# ws2812_Sqaure_V01.net
KiCad netlist of a schematic drawn in EAGLE
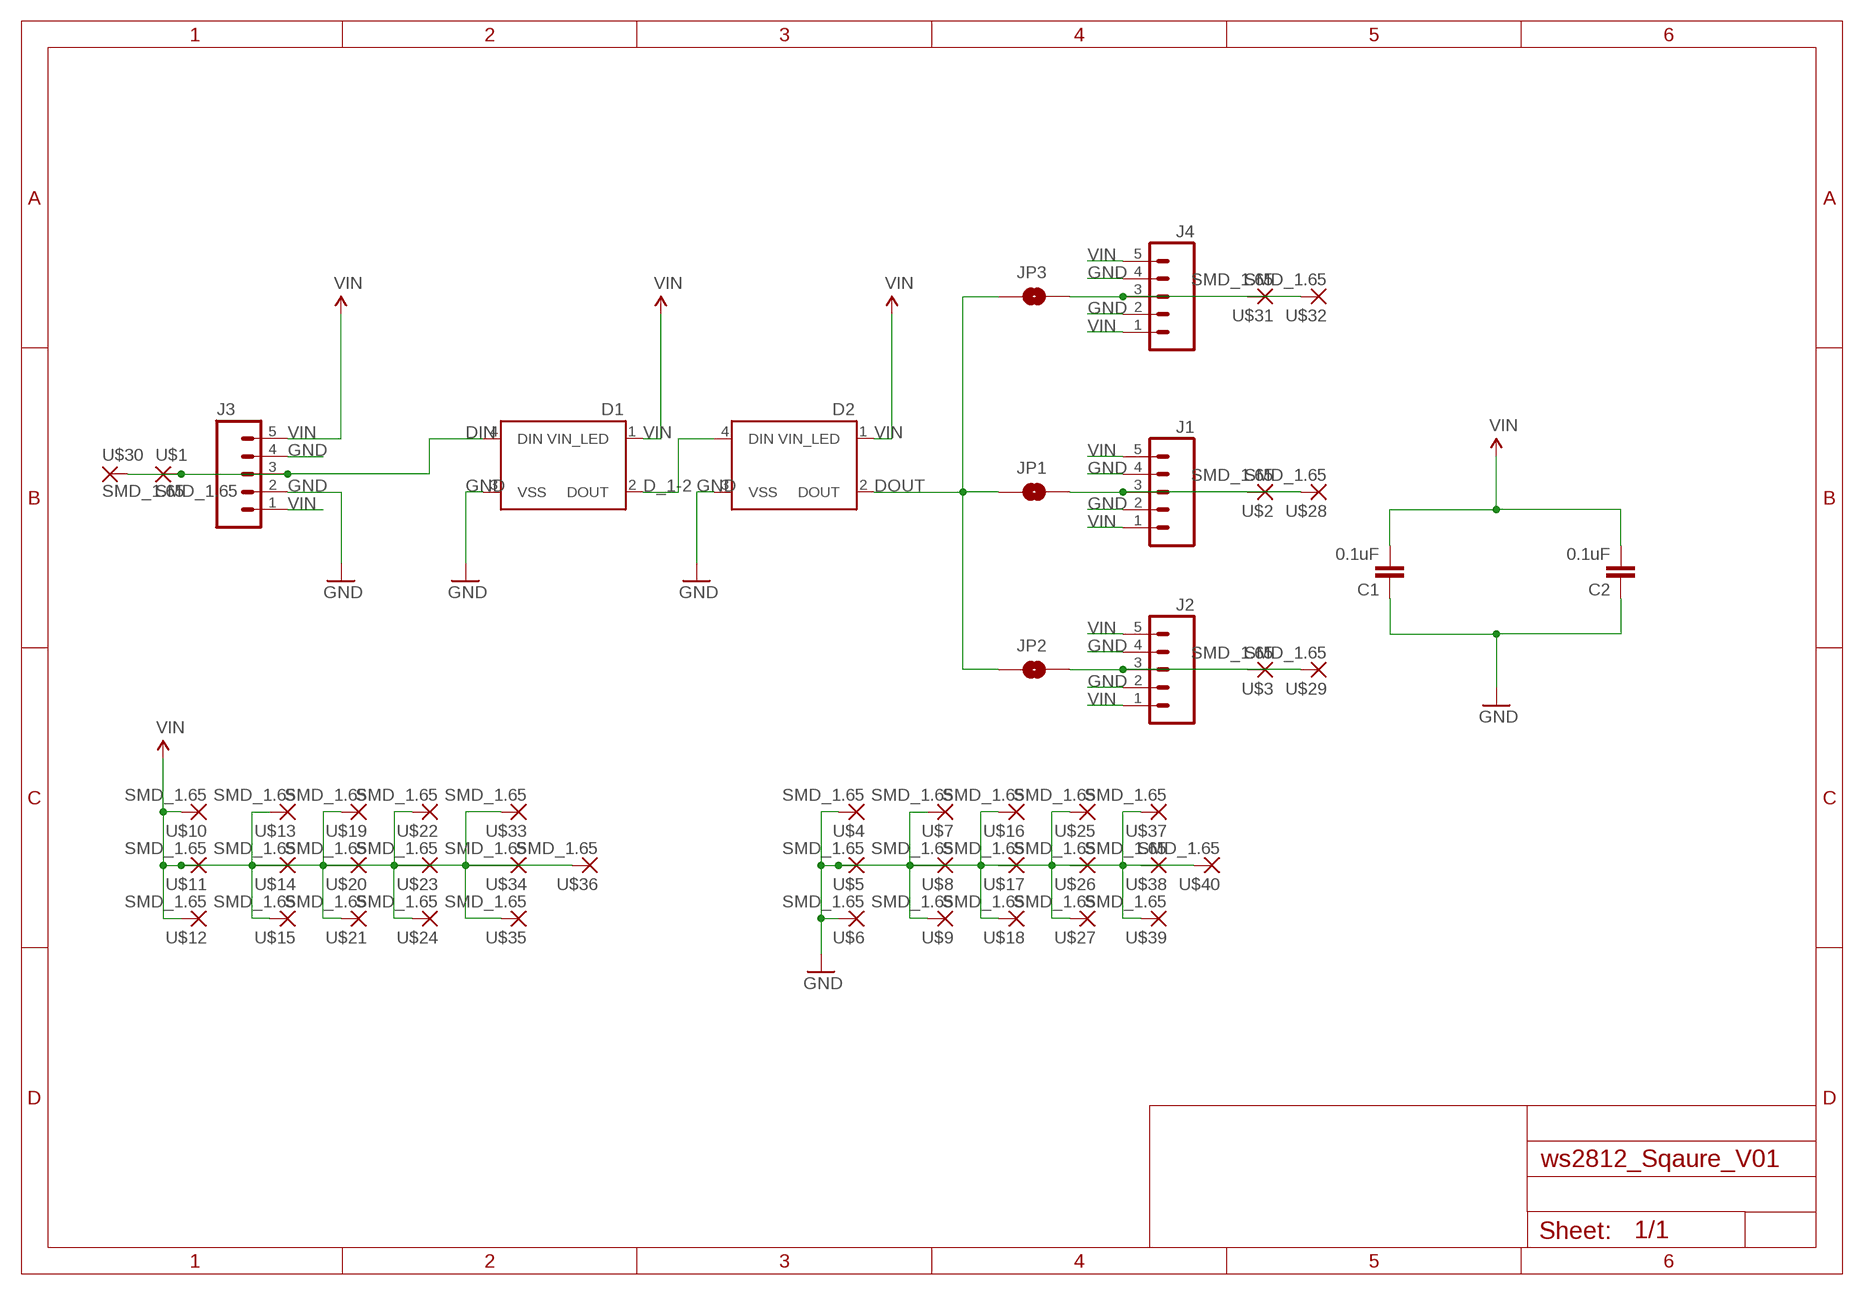
[diagram p0: schematic, sheet 1]

(export (version "E")
  (design (tool "Eeschema 10.0.6"))
  (components
    (comp (ref "C1")
      (value "0.1uF")
      (footprint "eagle-import:0805")
      (libsource (lib "eagle-import") (part "CAP0805"))
    )
    (comp (ref "C2")
      (value "0.1uF")
      (footprint "eagle-import:0805")
      (libsource (lib "eagle-import") (part "CAP0805"))
    )
    (comp (ref "D1")
      (value "WS2812B")
      (footprint "eagle-import:WS2812B")
      (libsource (lib "eagle-import") (part "WS2812B"))
    )
    (comp (ref "D2")
      (value "WS2812B")
      (footprint "eagle-import:WS2812B")
      (libsource (lib "eagle-import") (part "WS2812B"))
    )
    (comp (ref "J1")
      (value "M05NO_SILK")
      (footprint "eagle-import:1X05_NO_SILK")
      (libsource (lib "eagle-import") (part "M05NO_SILK"))
    )
    (comp (ref "J2")
      (value "M05NO_SILK")
      (footprint "eagle-import:1X05_NO_SILK")
      (libsource (lib "eagle-import") (part "M05NO_SILK"))
    )
    (comp (ref "J3")
      (value "M05NO_SILK")
      (footprint "eagle-import:1X05_NO_SILK")
      (libsource (lib "eagle-import") (part "M05NO_SILK"))
    )
    (comp (ref "J4")
      (value "M05NO_SILK")
      (footprint "eagle-import:1X05_NO_SILK")
      (libsource (lib "eagle-import") (part "M05NO_SILK"))
    )
    (comp (ref "JP1")
      (value "JUMPER-PAD-2-NOYES_SILK")
      (footprint "eagle-import:PAD-JUMPER-2-NO_YES_SILK")
      (libsource (lib "eagle-import") (part "JUMPER-PAD-2-NOYES_SILK"))
    )
    (comp (ref "JP2")
      (value "JUMPER-PAD-2-NOYES_SILK")
      (footprint "eagle-import:PAD-JUMPER-2-NO_YES_SILK")
      (libsource (lib "eagle-import") (part "JUMPER-PAD-2-NOYES_SILK"))
    )
    (comp (ref "JP3")
      (value "JUMPER-PAD-2-NOYES_SILK")
      (footprint "eagle-import:PAD-JUMPER-2-NO_YES_SILK")
      (libsource (lib "eagle-import") (part "JUMPER-PAD-2-NOYES_SILK"))
    )
    (comp (ref "U$1")
      (value "SMD_1.65")
      (footprint "eagle-import:SMD_PTH_1.65")
      (libsource (lib "eagle-import") (part "SMD_1.65"))
    )
    (comp (ref "U$2")
      (value "SMD_1.65")
      (footprint "eagle-import:SMD_PTH_1.65")
      (libsource (lib "eagle-import") (part "SMD_1.65"))
    )
    (comp (ref "U$3")
      (value "SMD_1.65")
      (footprint "eagle-import:SMD_PTH_1.65")
      (libsource (lib "eagle-import") (part "SMD_1.65"))
    )
    (comp (ref "U$4")
      (value "SMD_1.65")
      (footprint "eagle-import:SMD_PTH_1.65")
      (libsource (lib "eagle-import") (part "SMD_1.65"))
    )
    (comp (ref "U$5")
      (value "SMD_1.65")
      (footprint "eagle-import:SMD_PTH_1.65")
      (libsource (lib "eagle-import") (part "SMD_1.65"))
    )
    (comp (ref "U$6")
      (value "SMD_1.65")
      (footprint "eagle-import:SMD_PTH_1.65")
      (libsource (lib "eagle-import") (part "SMD_1.65"))
    )
    (comp (ref "U$7")
      (value "SMD_1.65")
      (footprint "eagle-import:SMD_PTH_1.65")
      (libsource (lib "eagle-import") (part "SMD_1.65"))
    )
    (comp (ref "U$8")
      (value "SMD_1.65")
      (footprint "eagle-import:SMD_PTH_1.65")
      (libsource (lib "eagle-import") (part "SMD_1.65"))
    )
    (comp (ref "U$9")
      (value "SMD_1.65")
      (footprint "eagle-import:SMD_PTH_1.65")
      (libsource (lib "eagle-import") (part "SMD_1.65"))
    )
    (comp (ref "U$10")
      (value "SMD_1.65")
      (footprint "eagle-import:SMD_PTH_1.65")
      (libsource (lib "eagle-import") (part "SMD_1.65"))
    )
    (comp (ref "U$11")
      (value "SMD_1.65")
      (footprint "eagle-import:SMD_PTH_1.65")
      (libsource (lib "eagle-import") (part "SMD_1.65"))
    )
    (comp (ref "U$12")
      (value "SMD_1.65")
      (footprint "eagle-import:SMD_PTH_1.65")
      (libsource (lib "eagle-import") (part "SMD_1.65"))
    )
    (comp (ref "U$13")
      (value "SMD_1.65")
      (footprint "eagle-import:SMD_PTH_1.65")
      (libsource (lib "eagle-import") (part "SMD_1.65"))
    )
    (comp (ref "U$14")
      (value "SMD_1.65")
      (footprint "eagle-import:SMD_PTH_1.65")
      (libsource (lib "eagle-import") (part "SMD_1.65"))
    )
    (comp (ref "U$15")
      (value "SMD_1.65")
      (footprint "eagle-import:SMD_PTH_1.65")
      (libsource (lib "eagle-import") (part "SMD_1.65"))
    )
    (comp (ref "U$16")
      (value "SMD_1.65")
      (footprint "eagle-import:SMD_PTH_1.65")
      (libsource (lib "eagle-import") (part "SMD_1.65"))
    )
    (comp (ref "U$17")
      (value "SMD_1.65")
      (footprint "eagle-import:SMD_PTH_1.65")
      (libsource (lib "eagle-import") (part "SMD_1.65"))
    )
    (comp (ref "U$18")
      (value "SMD_1.65")
      (footprint "eagle-import:SMD_PTH_1.65")
      (libsource (lib "eagle-import") (part "SMD_1.65"))
    )
    (comp (ref "U$19")
      (value "SMD_1.65")
      (footprint "eagle-import:SMD_PTH_1.65")
      (libsource (lib "eagle-import") (part "SMD_1.65"))
    )
    (comp (ref "U$20")
      (value "SMD_1.65")
      (footprint "eagle-import:SMD_PTH_1.65")
      (libsource (lib "eagle-import") (part "SMD_1.65"))
    )
    (comp (ref "U$21")
      (value "SMD_1.65")
      (footprint "eagle-import:SMD_PTH_1.65")
      (libsource (lib "eagle-import") (part "SMD_1.65"))
    )
    (comp (ref "U$22")
      (value "SMD_1.65")
      (footprint "eagle-import:SMD_PTH_1.65")
      (libsource (lib "eagle-import") (part "SMD_1.65"))
    )
    (comp (ref "U$23")
      (value "SMD_1.65")
      (footprint "eagle-import:SMD_PTH_1.65")
      (libsource (lib "eagle-import") (part "SMD_1.65"))
    )
    (comp (ref "U$24")
      (value "SMD_1.65")
      (footprint "eagle-import:SMD_PTH_1.65")
      (libsource (lib "eagle-import") (part "SMD_1.65"))
    )
    (comp (ref "U$25")
      (value "SMD_1.65")
      (footprint "eagle-import:SMD_PTH_1.65")
      (libsource (lib "eagle-import") (part "SMD_1.65"))
    )
    (comp (ref "U$26")
      (value "SMD_1.65")
      (footprint "eagle-import:SMD_PTH_1.65")
      (libsource (lib "eagle-import") (part "SMD_1.65"))
    )
    (comp (ref "U$27")
      (value "SMD_1.65")
      (footprint "eagle-import:SMD_PTH_1.65")
      (libsource (lib "eagle-import") (part "SMD_1.65"))
    )
    (comp (ref "U$28")
      (value "SMD_1.65")
      (footprint "eagle-import:SMD_PTH_1.65")
      (libsource (lib "eagle-import") (part "SMD_1.65"))
    )
    (comp (ref "U$29")
      (value "SMD_1.65")
      (footprint "eagle-import:SMD_PTH_1.65")
      (libsource (lib "eagle-import") (part "SMD_1.65"))
    )
    (comp (ref "U$30")
      (value "SMD_1.65")
      (footprint "eagle-import:SMD_PTH_1.65")
      (libsource (lib "eagle-import") (part "SMD_1.65"))
    )
    (comp (ref "U$31")
      (value "SMD_1.65")
      (footprint "eagle-import:SMD_PTH_1.65")
      (libsource (lib "eagle-import") (part "SMD_1.65"))
    )
    (comp (ref "U$32")
      (value "SMD_1.65")
      (footprint "eagle-import:SMD_PTH_1.65")
      (libsource (lib "eagle-import") (part "SMD_1.65"))
    )
    (comp (ref "U$33")
      (value "SMD_1.65")
      (footprint "eagle-import:SMD_PTH_1.65")
      (libsource (lib "eagle-import") (part "SMD_1.65"))
    )
    (comp (ref "U$34")
      (value "SMD_1.65")
      (footprint "eagle-import:SMD_PTH_1.65")
      (libsource (lib "eagle-import") (part "SMD_1.65"))
    )
    (comp (ref "U$35")
      (value "SMD_1.65")
      (footprint "eagle-import:SMD_PTH_1.65")
      (libsource (lib "eagle-import") (part "SMD_1.65"))
    )
    (comp (ref "U$36")
      (value "SMD_1.65")
      (footprint "eagle-import:SMD_PTH_1.65")
      (libsource (lib "eagle-import") (part "SMD_1.65"))
    )
    (comp (ref "U$37")
      (value "SMD_1.65")
      (footprint "eagle-import:SMD_PTH_1.65")
      (libsource (lib "eagle-import") (part "SMD_1.65"))
    )
    (comp (ref "U$38")
      (value "SMD_1.65")
      (footprint "eagle-import:SMD_PTH_1.65")
      (libsource (lib "eagle-import") (part "SMD_1.65"))
    )
    (comp (ref "U$39")
      (value "SMD_1.65")
      (footprint "eagle-import:SMD_PTH_1.65")
      (libsource (lib "eagle-import") (part "SMD_1.65"))
    )
    (comp (ref "U$40")
      (value "SMD_1.65")
      (footprint "eagle-import:SMD_PTH_1.65")
      (libsource (lib "eagle-import") (part "SMD_1.65"))
    )
  )
  (nets
    (net (code "1") (name "/DIN") (class "Default")
      (node (ref "D1") (pin "4") (pinfunction "DIN_4") (pintype "input"))
      (node (ref "J3") (pin "3") (pinfunction "3_3") (pintype "passive"))
      (node (ref "U$1") (pin "P$1") (pinfunction "P_P$1") (pintype "passive"))
      (node (ref "U$30") (pin "P$1") (pinfunction "P_P$1") (pintype "passive"))
    )
    (net (code "2") (name "/DOUT") (class "Default")
      (node (ref "D2") (pin "2") (pinfunction "DOUT_2") (pintype "output"))
      (node (ref "JP1") (pin "1") (pinfunction "1_1") (pintype "passive"))
      (node (ref "JP2") (pin "1") (pinfunction "1_1") (pintype "passive"))
      (node (ref "JP3") (pin "1") (pinfunction "1_1") (pintype "passive"))
    )
    (net (code "3") (name "/D_1-2") (class "Default")
      (node (ref "D1") (pin "2") (pinfunction "DOUT_2") (pintype "output"))
      (node (ref "D2") (pin "4") (pinfunction "DIN_4") (pintype "input"))
    )
    (net (code "4") (name "GND") (class "Default")
      (node (ref "C1") (pin "1") (pinfunction "1_1") (pintype "passive"))
      (node (ref "C2") (pin "1") (pinfunction "1_1") (pintype "passive"))
      (node (ref "D1") (pin "3") (pinfunction "VSS_3") (pintype "power_in"))
      (node (ref "D2") (pin "3") (pinfunction "VSS_3") (pintype "power_in"))
      (node (ref "J1") (pin "2") (pinfunction "2_2") (pintype "passive"))
      (node (ref "J1") (pin "4") (pinfunction "4_4") (pintype "passive"))
      (node (ref "J2") (pin "2") (pinfunction "2_2") (pintype "passive"))
      (node (ref "J2") (pin "4") (pinfunction "4_4") (pintype "passive"))
      (node (ref "J3") (pin "2") (pinfunction "2_2") (pintype "passive"))
      (node (ref "J3") (pin "4") (pinfunction "4_4") (pintype "passive"))
      (node (ref "J4") (pin "2") (pinfunction "2_2") (pintype "passive"))
      (node (ref "J4") (pin "4") (pinfunction "4_4") (pintype "passive"))
      (node (ref "U$16") (pin "P$1") (pinfunction "P_P$1") (pintype "passive"))
      (node (ref "U$17") (pin "P$1") (pinfunction "P_P$1") (pintype "passive"))
      (node (ref "U$18") (pin "P$1") (pinfunction "P_P$1") (pintype "passive"))
      (node (ref "U$25") (pin "P$1") (pinfunction "P_P$1") (pintype "passive"))
      (node (ref "U$26") (pin "P$1") (pinfunction "P_P$1") (pintype "passive"))
      (node (ref "U$27") (pin "P$1") (pinfunction "P_P$1") (pintype "passive"))
      (node (ref "U$37") (pin "P$1") (pinfunction "P_P$1") (pintype "passive"))
      (node (ref "U$38") (pin "P$1") (pinfunction "P_P$1") (pintype "passive"))
      (node (ref "U$39") (pin "P$1") (pinfunction "P_P$1") (pintype "passive"))
      (node (ref "U$4") (pin "P$1") (pinfunction "P_P$1") (pintype "passive"))
      (node (ref "U$40") (pin "P$1") (pinfunction "P_P$1") (pintype "passive"))
      (node (ref "U$5") (pin "P$1") (pinfunction "P_P$1") (pintype "passive"))
      (node (ref "U$6") (pin "P$1") (pinfunction "P_P$1") (pintype "passive"))
      (node (ref "U$7") (pin "P$1") (pinfunction "P_P$1") (pintype "passive"))
      (node (ref "U$8") (pin "P$1") (pinfunction "P_P$1") (pintype "passive"))
      (node (ref "U$9") (pin "P$1") (pinfunction "P_P$1") (pintype "passive"))
    )
    (net (code "5") (name "Net-(U$2-P)") (class "Default")
      (node (ref "J1") (pin "3") (pinfunction "3_3") (pintype "passive"))
      (node (ref "JP1") (pin "2") (pinfunction "2_2") (pintype "passive"))
      (node (ref "U$2") (pin "P$1") (pinfunction "P_P$1") (pintype "passive"))
      (node (ref "U$28") (pin "P$1") (pinfunction "P_P$1") (pintype "passive"))
    )
    (net (code "6") (name "Net-(U$29-P)") (class "Default")
      (node (ref "J2") (pin "3") (pinfunction "3_3") (pintype "passive"))
      (node (ref "JP2") (pin "2") (pinfunction "2_2") (pintype "passive"))
      (node (ref "U$29") (pin "P$1") (pinfunction "P_P$1") (pintype "passive"))
      (node (ref "U$3") (pin "P$1") (pinfunction "P_P$1") (pintype "passive"))
    )
    (net (code "7") (name "Net-(U$31-P)") (class "Default")
      (node (ref "J4") (pin "3") (pinfunction "3_3") (pintype "passive"))
      (node (ref "JP3") (pin "2") (pinfunction "2_2") (pintype "passive"))
      (node (ref "U$31") (pin "P$1") (pinfunction "P_P$1") (pintype "passive"))
      (node (ref "U$32") (pin "P$1") (pinfunction "P_P$1") (pintype "passive"))
    )
    (net (code "8") (name "VIN") (class "Default")
      (node (ref "C1") (pin "2") (pinfunction "2_2") (pintype "passive"))
      (node (ref "C2") (pin "2") (pinfunction "2_2") (pintype "passive"))
      (node (ref "D1") (pin "1") (pinfunction "VIN_LED_1") (pintype "power_in"))
      (node (ref "D2") (pin "1") (pinfunction "VIN_LED_1") (pintype "power_in"))
      (node (ref "J1") (pin "1") (pinfunction "1_1") (pintype "passive"))
      (node (ref "J1") (pin "5") (pinfunction "5_5") (pintype "passive"))
      (node (ref "J2") (pin "1") (pinfunction "1_1") (pintype "passive"))
      (node (ref "J2") (pin "5") (pinfunction "5_5") (pintype "passive"))
      (node (ref "J3") (pin "1") (pinfunction "1_1") (pintype "passive"))
      (node (ref "J3") (pin "5") (pinfunction "5_5") (pintype "passive"))
      (node (ref "J4") (pin "1") (pinfunction "1_1") (pintype "passive"))
      (node (ref "J4") (pin "5") (pinfunction "5_5") (pintype "passive"))
      (node (ref "U$10") (pin "P$1") (pinfunction "P_P$1") (pintype "passive"))
      (node (ref "U$11") (pin "P$1") (pinfunction "P_P$1") (pintype "passive"))
      (node (ref "U$12") (pin "P$1") (pinfunction "P_P$1") (pintype "passive"))
      (node (ref "U$13") (pin "P$1") (pinfunction "P_P$1") (pintype "passive"))
      (node (ref "U$14") (pin "P$1") (pinfunction "P_P$1") (pintype "passive"))
      (node (ref "U$15") (pin "P$1") (pinfunction "P_P$1") (pintype "passive"))
      (node (ref "U$19") (pin "P$1") (pinfunction "P_P$1") (pintype "passive"))
      (node (ref "U$20") (pin "P$1") (pinfunction "P_P$1") (pintype "passive"))
      (node (ref "U$21") (pin "P$1") (pinfunction "P_P$1") (pintype "passive"))
      (node (ref "U$22") (pin "P$1") (pinfunction "P_P$1") (pintype "passive"))
      (node (ref "U$23") (pin "P$1") (pinfunction "P_P$1") (pintype "passive"))
      (node (ref "U$24") (pin "P$1") (pinfunction "P_P$1") (pintype "passive"))
      (node (ref "U$33") (pin "P$1") (pinfunction "P_P$1") (pintype "passive"))
      (node (ref "U$34") (pin "P$1") (pinfunction "P_P$1") (pintype "passive"))
      (node (ref "U$35") (pin "P$1") (pinfunction "P_P$1") (pintype "passive"))
      (node (ref "U$36") (pin "P$1") (pinfunction "P_P$1") (pintype "passive"))
    )
  )
)
